# qpot.net
KiCad netlist of a schematic drawn in EAGLE
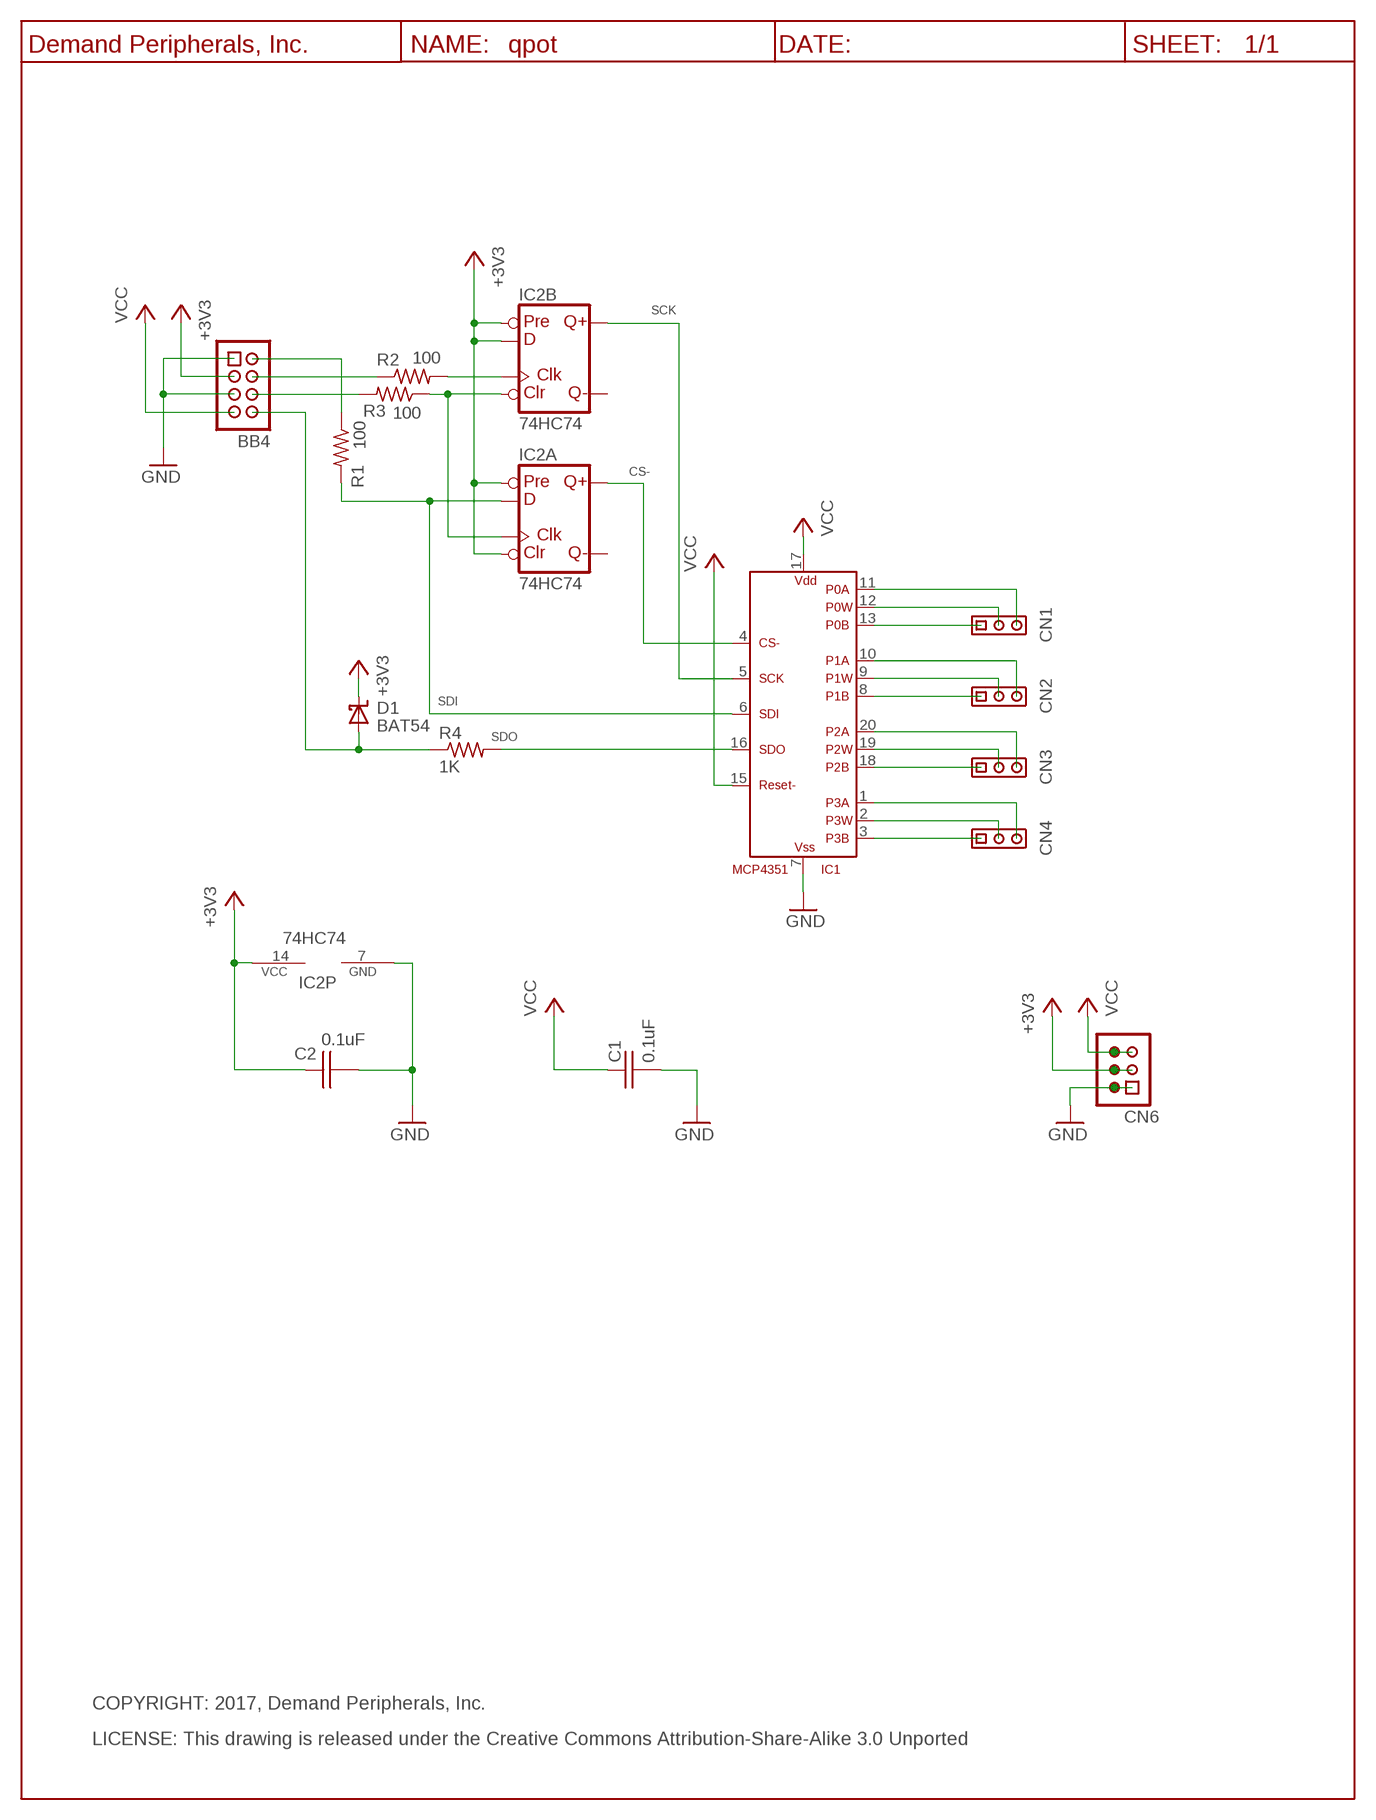
[diagram p0: schematic, sheet 1]

(export (version "E")
  (design (tool "Eeschema 10.0.6"))
  (components
    (comp (ref "BB4")
      (value "BB_CON")
      (footprint "eagle-import:HDR-4X2")
      (libsource (lib "eagle-import") (part "HDR-4X2-SHR"))
    )
    (comp (ref "C1")
      (value "0.1uF")
      (footprint "eagle-import:C0603")
      (libsource (lib "eagle-import") (part "C0.1UF_C0603"))
    )
    (comp (ref "C2")
      (value "0.1uF")
      (footprint "eagle-import:C0603")
      (libsource (lib "eagle-import") (part "C0.1UF_C0603"))
    )
    (comp (ref "CN1")
      (value "HDR-3X1")
      (footprint "eagle-import:HDR-3X1")
      (libsource (lib "eagle-import") (part "HDR-3X1"))
    )
    (comp (ref "CN2")
      (value "HDR-3X1")
      (footprint "eagle-import:HDR-3X1")
      (libsource (lib "eagle-import") (part "HDR-3X1"))
    )
    (comp (ref "CN3")
      (value "HDR-3X1")
      (footprint "eagle-import:HDR-3X1")
      (libsource (lib "eagle-import") (part "HDR-3X1"))
    )
    (comp (ref "CN4")
      (value "HDR-3X1")
      (footprint "eagle-import:HDR-3X1")
      (libsource (lib "eagle-import") (part "HDR-3X1"))
    )
    (comp (ref "CN6")
      (value "HDR-3X2")
      (footprint "eagle-import:HDR-3X2")
      (libsource (lib "eagle-import") (part "HDR-3X2"))
    )
    (comp (ref "D1")
      (value "BAT54")
      (footprint "eagle-import:SOT23")
      (libsource (lib "eagle-import") (part "BAT54"))
    )
    (comp (ref "IC1")
      (value "MCP4351")
      (footprint "eagle-import:TSSOP20")
      (libsource (lib "eagle-import") (part "MCP4351"))
    )
    (comp (ref "IC2")
      (value "74HC74")
      (footprint "eagle-import:SO14")
      (libsource (lib "eagle-import") (part "74AHC74SS"))
    )
    (comp (ref "R1")
      (value "100")
      (footprint "eagle-import:R0603")
      (libsource (lib "eagle-import") (part "R100_R0603"))
    )
    (comp (ref "R2")
      (value "100")
      (footprint "eagle-import:R0603")
      (libsource (lib "eagle-import") (part "R100_R0603"))
    )
    (comp (ref "R3")
      (value "100")
      (footprint "eagle-import:R0603")
      (libsource (lib "eagle-import") (part "R100_R0603"))
    )
    (comp (ref "R4")
      (value "1K")
      (footprint "eagle-import:R0603")
      (libsource (lib "eagle-import") (part "R1K_R0603"))
    )
    (comp (ref "U$3")
      (value "DP_FRAME_P")
      (footprint "eagle-import:P_FRAME")
      (libsource (lib "eagle-import") (part "DP_FRAME_P"))
    )
  )
  (nets
    (net (code "1") (name "+3V3") (class "Default")
      (node (ref "BB4") (pin "3") (pinfunction "3_3") (pintype "passive"))
      (node (ref "C2") (pin "1") (pinfunction "1_1") (pintype "passive"))
      (node (ref "CN6") (pin "3") (pinfunction "3_3") (pintype "passive"))
      (node (ref "CN6") (pin "4") (pinfunction "4_4") (pintype "passive"))
      (node (ref "D1") (pin "3") (pinfunction "CC_3") (pintype "passive"))
      (node (ref "IC2") (pin "1") (pinfunction "CLR_1") (pintype "input"))
      (node (ref "IC2") (pin "10") (pinfunction "PRE_10") (pintype "input"))
      (node (ref "IC2") (pin "12") (pinfunction "D_12") (pintype "input"))
      (node (ref "IC2") (pin "14") (pinfunction "VCC_14") (pintype "power_in"))
      (node (ref "IC2") (pin "4") (pinfunction "PRE_4") (pintype "input"))
    )
    (net (code "2") (name "GND") (class "Default")
      (node (ref "BB4") (pin "1") (pinfunction "1_1") (pintype "passive"))
      (node (ref "BB4") (pin "5") (pinfunction "5_5") (pintype "passive"))
      (node (ref "C1") (pin "2") (pinfunction "2_2") (pintype "passive"))
      (node (ref "C2") (pin "2") (pinfunction "2_2") (pintype "passive"))
      (node (ref "CN6") (pin "1") (pinfunction "1_1") (pintype "passive"))
      (node (ref "CN6") (pin "2") (pinfunction "2_2") (pintype "passive"))
      (node (ref "IC1") (pin "7") (pinfunction "VSS_7") (pintype "power_in"))
      (node (ref "IC2") (pin "7") (pinfunction "GND_7") (pintype "power_in"))
    )
    (net (code "3") (name "Net-(BB4-Pad2)") (class "Default")
      (node (ref "BB4") (pin "2") (pinfunction "2_2") (pintype "passive"))
      (node (ref "R1") (pin "1") (pinfunction "1_1") (pintype "passive"))
    )
    (net (code "4") (name "Net-(BB4-Pad4)") (class "Default")
      (node (ref "BB4") (pin "4") (pinfunction "4_4") (pintype "passive"))
      (node (ref "R2") (pin "1") (pinfunction "1_1") (pintype "passive"))
    )
    (net (code "5") (name "Net-(BB4-Pad6)") (class "Default")
      (node (ref "BB4") (pin "6") (pinfunction "6_6") (pintype "passive"))
      (node (ref "R3") (pin "2") (pinfunction "2_2") (pintype "passive"))
    )
    (net (code "6") (name "Net-(D1-A)") (class "Default")
      (node (ref "BB4") (pin "8") (pinfunction "8_8") (pintype "passive"))
      (node (ref "D1") (pin "1") (pinfunction "A_1") (pintype "passive"))
      (node (ref "R4") (pin "1") (pinfunction "1_1") (pintype "passive"))
    )
    (net (code "7") (name "Net-(IC1-CS-)") (class "Default")
      (node (ref "IC1") (pin "4") (pinfunction "CS-_4") (pintype "input"))
      (node (ref "IC2") (pin "5") (pinfunction "Q_5") (pintype "output"))
    )
    (net (code "8") (name "Net-(IC1-P0A)") (class "Default")
      (node (ref "CN1") (pin "3") (pinfunction "3_3") (pintype "passive"))
      (node (ref "IC1") (pin "11") (pinfunction "P0A_11") (pintype "passive"))
    )
    (net (code "9") (name "Net-(IC1-P0B)") (class "Default")
      (node (ref "CN1") (pin "1") (pinfunction "1_1") (pintype "passive"))
      (node (ref "IC1") (pin "13") (pinfunction "P0B_13") (pintype "passive"))
    )
    (net (code "10") (name "Net-(IC1-P0W)") (class "Default")
      (node (ref "CN1") (pin "2") (pinfunction "2_2") (pintype "passive"))
      (node (ref "IC1") (pin "12") (pinfunction "P0W_12") (pintype "passive"))
    )
    (net (code "11") (name "Net-(IC1-P1A)") (class "Default")
      (node (ref "CN2") (pin "3") (pinfunction "3_3") (pintype "passive"))
      (node (ref "IC1") (pin "10") (pinfunction "P1A_10") (pintype "passive"))
    )
    (net (code "12") (name "Net-(IC1-P1B)") (class "Default")
      (node (ref "CN2") (pin "1") (pinfunction "1_1") (pintype "passive"))
      (node (ref "IC1") (pin "8") (pinfunction "P1B_8") (pintype "passive"))
    )
    (net (code "13") (name "Net-(IC1-P1W)") (class "Default")
      (node (ref "CN2") (pin "2") (pinfunction "2_2") (pintype "passive"))
      (node (ref "IC1") (pin "9") (pinfunction "P1W_9") (pintype "passive"))
    )
    (net (code "14") (name "Net-(IC1-P2A)") (class "Default")
      (node (ref "CN3") (pin "3") (pinfunction "3_3") (pintype "passive"))
      (node (ref "IC1") (pin "20") (pinfunction "P2A_20") (pintype "passive"))
    )
    (net (code "15") (name "Net-(IC1-P2B)") (class "Default")
      (node (ref "CN3") (pin "1") (pinfunction "1_1") (pintype "passive"))
      (node (ref "IC1") (pin "18") (pinfunction "P2B_18") (pintype "passive"))
    )
    (net (code "16") (name "Net-(IC1-P2W)") (class "Default")
      (node (ref "CN3") (pin "2") (pinfunction "2_2") (pintype "passive"))
      (node (ref "IC1") (pin "19") (pinfunction "P2W_19") (pintype "passive"))
    )
    (net (code "17") (name "Net-(IC1-P3A)") (class "Default")
      (node (ref "CN4") (pin "3") (pinfunction "3_3") (pintype "passive"))
      (node (ref "IC1") (pin "1") (pinfunction "P3A_1") (pintype "passive"))
    )
    (net (code "18") (name "Net-(IC1-P3B)") (class "Default")
      (node (ref "CN4") (pin "1") (pinfunction "1_1") (pintype "passive"))
      (node (ref "IC1") (pin "3") (pinfunction "P3B_3") (pintype "passive"))
    )
    (net (code "19") (name "Net-(IC1-P3W)") (class "Default")
      (node (ref "CN4") (pin "2") (pinfunction "2_2") (pintype "passive"))
      (node (ref "IC1") (pin "2") (pinfunction "P3W_2") (pintype "passive"))
    )
    (net (code "20") (name "Net-(IC1-SCK)") (class "Default")
      (node (ref "IC1") (pin "5") (pinfunction "SCK_5") (pintype "input"))
      (node (ref "IC2") (pin "9") (pinfunction "Q_9") (pintype "output"))
    )
    (net (code "21") (name "Net-(IC1-SDI)") (class "Default")
      (node (ref "IC1") (pin "6") (pinfunction "SDI_6") (pintype "input"))
      (node (ref "IC2") (pin "2") (pinfunction "D_2") (pintype "input"))
      (node (ref "R1") (pin "2") (pinfunction "2_2") (pintype "passive"))
    )
    (net (code "22") (name "Net-(IC1-SDO)") (class "Default")
      (node (ref "IC1") (pin "16") (pinfunction "SDO_16") (pintype "output"))
      (node (ref "R4") (pin "2") (pinfunction "2_2") (pintype "passive"))
    )
    (net (code "23") (name "Net-(IC2A-CLK)") (class "Default")
      (node (ref "IC2") (pin "13") (pinfunction "CLR_13") (pintype "input"))
      (node (ref "IC2") (pin "3") (pinfunction "CLK_3") (pintype "input"))
      (node (ref "R3") (pin "1") (pinfunction "1_1") (pintype "passive"))
    )
    (net (code "24") (name "Net-(IC2B-CLK)") (class "Default")
      (node (ref "IC2") (pin "11") (pinfunction "CLK_11") (pintype "input"))
      (node (ref "R2") (pin "2") (pinfunction "2_2") (pintype "passive"))
    )
    (net (code "25") (name "VCC") (class "Default")
      (node (ref "BB4") (pin "7") (pinfunction "7_7") (pintype "passive"))
      (node (ref "C1") (pin "1") (pinfunction "1_1") (pintype "passive"))
      (node (ref "CN6") (pin "5") (pinfunction "5_5") (pintype "passive"))
      (node (ref "CN6") (pin "6") (pinfunction "6_6") (pintype "passive"))
      (node (ref "IC1") (pin "15") (pinfunction "RESET-_15") (pintype "input"))
      (node (ref "IC1") (pin "17") (pinfunction "VDD_17") (pintype "power_in"))
    )
    (net (code "26") (name "unconnected-(IC2A-~{Q}-Pad6)") (class "Default")
      (node (ref "IC2") (pin "6") (pinfunction "~{Q}_6") (pintype "output"))
    )
    (net (code "27") (name "unconnected-(IC2B-~{Q}-Pad8)") (class "Default")
      (node (ref "IC2") (pin "8") (pinfunction "~{Q}_8") (pintype "output"))
    )
  )
)
